# CircuitDiagram.net
KiCad netlist of a schematic drawn in EAGLE
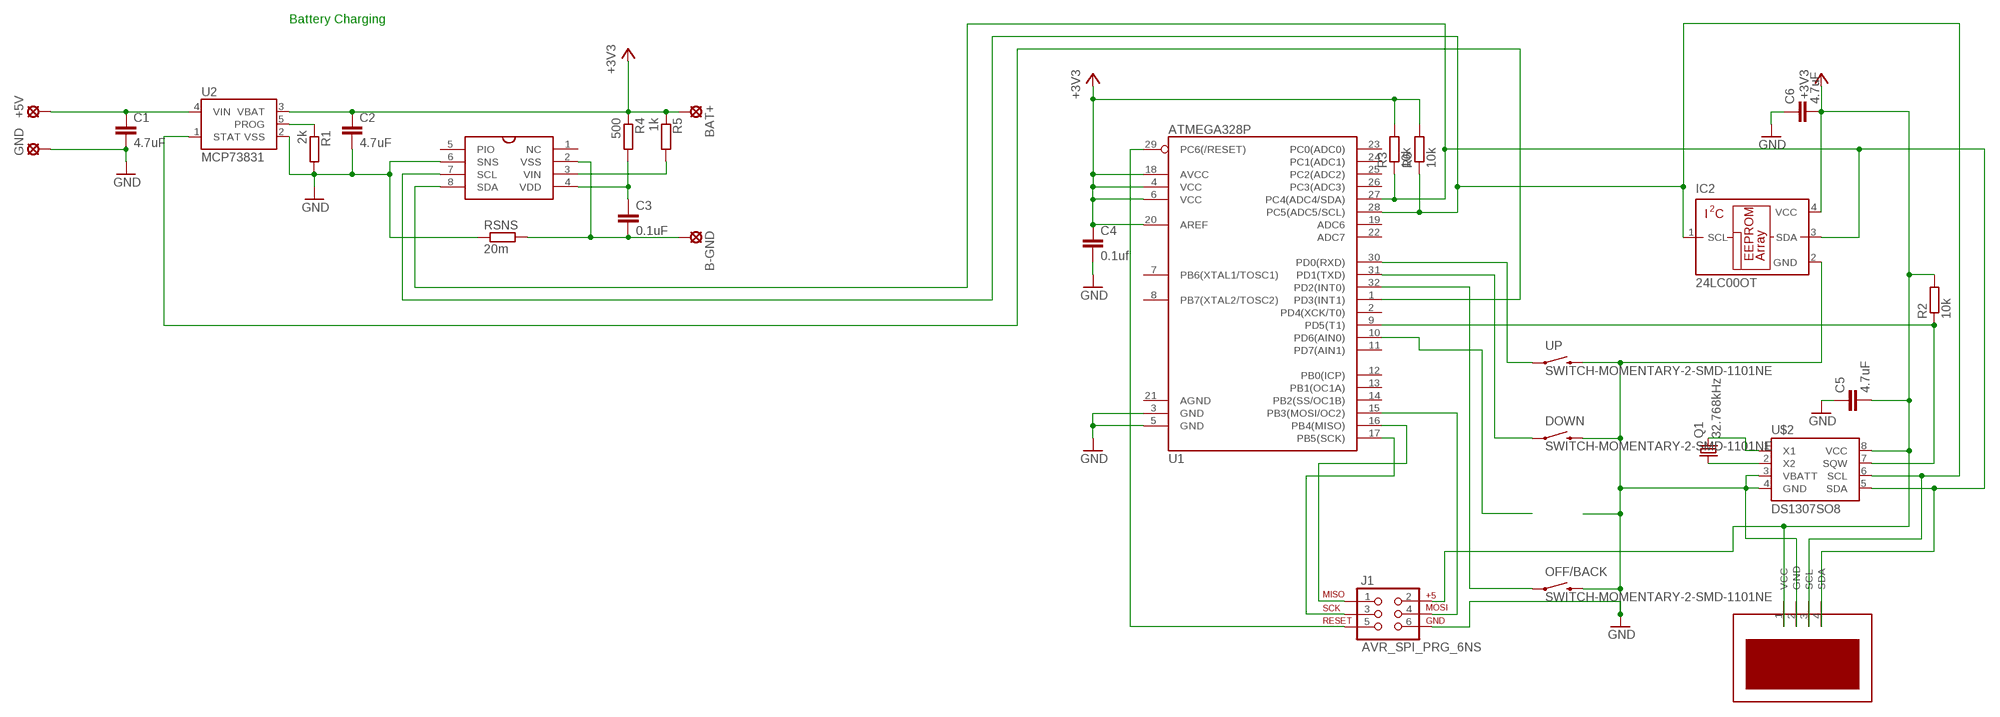
[diagram p0: schematic, sheet 1]

(export (version "E")
  (design (tool "Eeschema 10.0.6"))
  (components
    (comp (ref "+5V")
      (value "LSP10")
      (footprint "eagle-import:LSP10")
      (libsource (lib "eagle-import") (part "LSP10"))
    )
    (comp (ref "B-GND")
      (value "LSP10")
      (footprint "eagle-import:LSP10")
      (libsource (lib "eagle-import") (part "LSP10"))
    )
    (comp (ref "BAT+")
      (value "LSP10")
      (footprint "eagle-import:LSP10")
      (libsource (lib "eagle-import") (part "LSP10"))
    )
    (comp (ref "C1")
      (value "4.7uF")
      (footprint "eagle-import:C0402")
      (libsource (lib "eagle-import") (part "C-EUC0402"))
    )
    (comp (ref "C2")
      (value "4.7uF")
      (footprint "eagle-import:C0402")
      (libsource (lib "eagle-import") (part "C-EUC0402"))
    )
    (comp (ref "C3")
      (value "0.1uF")
      (footprint "eagle-import:C0402")
      (libsource (lib "eagle-import") (part "C-EUC0402"))
    )
    (comp (ref "C4")
      (value "0.1uf")
      (footprint "eagle-import:C0402")
      (libsource (lib "eagle-import") (part "C-EUC0402"))
    )
    (comp (ref "C5")
      (value "4.7uF")
      (footprint "eagle-import:C0402")
      (libsource (lib "eagle-import") (part "C-EUC0402"))
    )
    (comp (ref "C6")
      (value "4.7uF")
      (footprint "eagle-import:C1005")
      (libsource (lib "eagle-import") (part "C-EUC1005"))
    )
    (comp (ref "DOWN")
      (value "SWITCH-MOMENTARY-2-SMD-1101NE")
      (footprint "eagle-import:TACTILE-SWITCH-1101NE")
      (libsource (lib "eagle-import") (part "SWITCH-MOMENTARY-2-SMD-1101NE"))
    )
    (comp (ref "GND")
      (value "LSP10")
      (footprint "eagle-import:LSP10")
      (libsource (lib "eagle-import") (part "LSP10"))
    )
    (comp (ref "IC2")
      (value "24LC00OT")
      (footprint "eagle-import:SOT23-5L")
      (fields (field (name "MF") "MICROCHIP") (field (name "MPN") "24LC00T-I/OT"))
      (libsource (lib "eagle-import") (part "2400OTLC"))
    )
    (comp (ref "J1")
      (value "AVR_SPI_PRG_6NS")
      (footprint "eagle-import:2X3-NS")
      (libsource (lib "eagle-import") (part "AVR_SPI_PRG_6NS"))
    )
    (comp (ref "OFF/BACK")
      (value "SWITCH-MOMENTARY-2-SMD-1101NE")
      (footprint "eagle-import:TACTILE-SWITCH-1101NE")
      (libsource (lib "eagle-import") (part "SWITCH-MOMENTARY-2-SMD-1101NE"))
    )
    (comp (ref "Q1")
      (value "32.768kHz")
      (footprint "eagle-import:3.2X1.5-2-PAD")
      (libsource (lib "eagle-import") (part "CRYSTALS-NOGND-CFPX-217"))
    )
    (comp (ref "R1")
      (value "2k")
      (footprint "eagle-import:R0603")
      (libsource (lib "eagle-import") (part "R-EU_R0603"))
    )
    (comp (ref "R2")
      (value "10k")
      (footprint "eagle-import:R0603")
      (libsource (lib "eagle-import") (part "R-EU_R0603"))
    )
    (comp (ref "R3")
      (value "10k")
      (footprint "eagle-import:R0603")
      (libsource (lib "eagle-import") (part "R-EU_R0603"))
    )
    (comp (ref "R4")
      (value "500")
      (footprint "eagle-import:R0603")
      (libsource (lib "eagle-import") (part "R-EU_R0603"))
    )
    (comp (ref "R5")
      (value "1k")
      (footprint "eagle-import:R0603")
      (libsource (lib "eagle-import") (part "R-EU_R0603"))
    )
    (comp (ref "R6")
      (value "10k")
      (footprint "eagle-import:R0603")
      (libsource (lib "eagle-import") (part "R-EU_R0603"))
    )
    (comp (ref "RSNS")
      (value "20m")
      (footprint "eagle-import:R0603")
      (libsource (lib "eagle-import") (part "R-EU_R0603"))
    )
    (comp (ref "U$1")
      (value "DS2782-2")
      (footprint "eagle-import:TSSOP8")
      (libsource (lib "eagle-import") (part "DS2782-2"))
    )
    (comp (ref "U$2")
      (value "DS1307SO8")
      (footprint "eagle-import:SO08")
      (libsource (lib "eagle-import") (part "DS1307SO8"))
    )
    (comp (ref "U$3")
      (value "OLED")
      (footprint "eagle-import:OLED")
      (libsource (lib "eagle-import") (part "OLED"))
    )
    (comp (ref "U1")
      (value "ATMEGA328P")
      (footprint "eagle-import:TQFP32-08")
      (libsource (lib "eagle-import") (part "ATMEGA328_SMT"))
    )
    (comp (ref "U2")
      (value "MCP73831")
      (footprint "eagle-import:SOT23-5")
      (libsource (lib "eagle-import") (part "MCP73831"))
    )
    (comp (ref "UP")
      (value "SWITCH-MOMENTARY-2-SMD-1101NE")
      (footprint "eagle-import:TACTILE-SWITCH-1101NE")
      (libsource (lib "eagle-import") (part "SWITCH-MOMENTARY-2-SMD-1101NE"))
    )
  )
  (nets
    (net (code "1") (name "+3V3") (class "Default")
      (node (ref "BAT+") (pin "MP") (pinfunction "MP_MP") (pintype "passive"))
      (node (ref "C2") (pin "1") (pinfunction "1_1") (pintype "passive"))
      (node (ref "C4") (pin "1") (pinfunction "1_1") (pintype "passive"))
      (node (ref "C5") (pin "2") (pinfunction "2_2") (pintype "passive"))
      (node (ref "C6") (pin "2") (pinfunction "2_2") (pintype "passive"))
      (node (ref "IC2") (pin "4") (pinfunction "VCC_4") (pintype "power_in"))
      (node (ref "J1") (pin "2") (pinfunction "2_2") (pintype "passive"))
      (node (ref "R2") (pin "2") (pinfunction "2_2") (pintype "passive"))
      (node (ref "R3") (pin "2") (pinfunction "2_2") (pintype "passive"))
      (node (ref "R4") (pin "1") (pinfunction "1_1") (pintype "passive"))
      (node (ref "R5") (pin "1") (pinfunction "1_1") (pintype "passive"))
      (node (ref "R6") (pin "2") (pinfunction "2_2") (pintype "passive"))
      (node (ref "U$2") (pin "8") (pinfunction "VCC_8") (pintype "bidirectional"))
      (node (ref "U$3") (pin "1") (pinfunction "VCC_1") (pintype "bidirectional"))
      (node (ref "U1") (pin "18") (pinfunction "AVCC_18") (pintype "bidirectional"))
      (node (ref "U1") (pin "20") (pinfunction "AREF_20") (pintype "bidirectional"))
      (node (ref "U1") (pin "4") (pinfunction "VCC_4") (pintype "bidirectional"))
      (node (ref "U1") (pin "6") (pinfunction "VCC_6") (pintype "bidirectional"))
      (node (ref "U2") (pin "3") (pinfunction "VBAT_3") (pintype "power_in"))
    )
    (net (code "2") (name "GND") (class "Default")
      (node (ref "C1") (pin "2") (pinfunction "2_2") (pintype "passive"))
      (node (ref "C2") (pin "2") (pinfunction "2_2") (pintype "passive"))
      (node (ref "C4") (pin "2") (pinfunction "2_2") (pintype "passive"))
      (node (ref "C5") (pin "1") (pinfunction "1_1") (pintype "passive"))
      (node (ref "C6") (pin "1") (pinfunction "1_1") (pintype "passive"))
      (node (ref "DOWN") (pin "2") (pinfunction "2_2") (pintype "passive"))
      (node (ref "GND") (pin "MP") (pinfunction "MP_MP") (pintype "passive"))
      (node (ref "IC2") (pin "2") (pinfunction "GND_2") (pintype "power_in"))
      (node (ref "J1") (pin "6") (pinfunction "6_6") (pintype "passive"))
      (node (ref "OFF/BACK") (pin "2") (pinfunction "2_2") (pintype "passive"))
      (node (ref "R1") (pin "2") (pinfunction "2_2") (pintype "passive"))
      (node (ref "RSNS") (pin "1") (pinfunction "1_1") (pintype "passive"))
      (node (ref "U$1") (pin "6") (pinfunction "SNS_6") (pintype "bidirectional"))
      (node (ref "U$2") (pin "3") (pinfunction "VBATT_3") (pintype "bidirectional"))
      (node (ref "U$2") (pin "4") (pinfunction "GND_4") (pintype "bidirectional"))
      (node (ref "U$3") (pin "2") (pinfunction "GND_2") (pintype "bidirectional"))
      (node (ref "U1") (pin "3") (pinfunction "GND_3") (pintype "bidirectional"))
      (node (ref "U1") (pin "5") (pinfunction "GND_5") (pintype "bidirectional"))
      (node (ref "U2") (pin "2") (pinfunction "VSS_2") (pintype "power_in"))
      (node (ref "UP") (pin "2") (pinfunction "2_2") (pintype "passive"))
    )
    (net (code "3") (name "Net-(IC2-SCL)") (class "Default")
      (node (ref "IC2") (pin "1") (pinfunction "SCL_1") (pintype "input"))
      (node (ref "R6") (pin "1") (pinfunction "1_1") (pintype "passive"))
      (node (ref "U$1") (pin "7") (pinfunction "SCL_7") (pintype "bidirectional"))
      (node (ref "U$2") (pin "6") (pinfunction "SCL_6") (pintype "bidirectional"))
      (node (ref "U$3") (pin "3") (pinfunction "SCL_3") (pintype "bidirectional"))
      (node (ref "U1") (pin "28") (pinfunction "PC5(ADC5/SCL)_28") (pintype "bidirectional"))
    )
    (net (code "4") (name "Net-(IC2-SDA)") (class "Default")
      (node (ref "IC2") (pin "3") (pinfunction "SDA_3") (pintype "bidirectional"))
      (node (ref "R3") (pin "1") (pinfunction "1_1") (pintype "passive"))
      (node (ref "U$1") (pin "8") (pinfunction "SDA_8") (pintype "bidirectional"))
      (node (ref "U$2") (pin "5") (pinfunction "SDA_5") (pintype "bidirectional"))
      (node (ref "U$3") (pin "4") (pinfunction "SDA_4") (pintype "bidirectional"))
      (node (ref "U1") (pin "27") (pinfunction "PC4(ADC4/SDA)_27") (pintype "bidirectional"))
    )
    (net (code "5") (name "Net-(U$1-VDD)") (class "Default")
      (node (ref "C3") (pin "1") (pinfunction "1_1") (pintype "passive"))
      (node (ref "R4") (pin "2") (pinfunction "2_2") (pintype "passive"))
      (node (ref "U$1") (pin "4") (pinfunction "VDD_4") (pintype "bidirectional"))
    )
    (net (code "6") (name "Net-(U$1-VIN)") (class "Default")
      (node (ref "R5") (pin "2") (pinfunction "2_2") (pintype "passive"))
      (node (ref "U$1") (pin "3") (pinfunction "VIN_3") (pintype "bidirectional"))
    )
    (net (code "7") (name "Net-(U$1-VSS)") (class "Default")
      (node (ref "B-GND") (pin "MP") (pinfunction "MP_MP") (pintype "passive"))
      (node (ref "C3") (pin "2") (pinfunction "2_2") (pintype "passive"))
      (node (ref "RSNS") (pin "2") (pinfunction "2_2") (pintype "passive"))
      (node (ref "U$1") (pin "2") (pinfunction "VSS_2") (pintype "bidirectional"))
    )
    (net (code "8") (name "Net-(U$2-SQW)") (class "Default")
      (node (ref "R2") (pin "1") (pinfunction "1_1") (pintype "passive"))
      (node (ref "U$2") (pin "7") (pinfunction "SQW_7") (pintype "bidirectional"))
      (node (ref "U1") (pin "9") (pinfunction "PD5(T1)_9") (pintype "bidirectional"))
    )
    (net (code "9") (name "Net-(U$2-X1)") (class "Default")
      (node (ref "Q1") (pin "2") (pinfunction "2_2") (pintype "passive"))
      (node (ref "U$2") (pin "1") (pinfunction "X1_1") (pintype "bidirectional"))
    )
    (net (code "10") (name "Net-(U$2-X2)") (class "Default")
      (node (ref "Q1") (pin "1") (pinfunction "1_1") (pintype "passive"))
      (node (ref "U$2") (pin "2") (pinfunction "X2_2") (pintype "bidirectional"))
    )
    (net (code "11") (name "Net-(U1-PB3(MOSI{slash}OC2))") (class "Default")
      (node (ref "J1") (pin "4") (pinfunction "4_4") (pintype "passive"))
      (node (ref "U1") (pin "15") (pinfunction "PB3(MOSI/OC2)_15") (pintype "bidirectional"))
    )
    (net (code "12") (name "Net-(U1-PB4(MISO))") (class "Default")
      (node (ref "J1") (pin "1") (pinfunction "1_1") (pintype "passive"))
      (node (ref "U1") (pin "16") (pinfunction "PB4(MISO)_16") (pintype "bidirectional"))
    )
    (net (code "13") (name "Net-(U1-PB5(SCK))") (class "Default")
      (node (ref "J1") (pin "3") (pinfunction "3_3") (pintype "passive"))
      (node (ref "U1") (pin "17") (pinfunction "PB5(SCK)_17") (pintype "bidirectional"))
    )
    (net (code "14") (name "Net-(U1-PC6({slash}RESET))") (class "Default")
      (node (ref "J1") (pin "5") (pinfunction "5_5") (pintype "passive"))
      (node (ref "U1") (pin "29") (pinfunction "PC6(/RESET)_29") (pintype "bidirectional"))
    )
    (net (code "15") (name "Net-(U1-PD0(RXD))") (class "Default")
      (node (ref "U1") (pin "30") (pinfunction "PD0(RXD)_30") (pintype "bidirectional"))
      (node (ref "UP") (pin "1") (pinfunction "1_1") (pintype "passive"))
    )
    (net (code "16") (name "Net-(U1-PD1(TXD))") (class "Default")
      (node (ref "DOWN") (pin "1") (pinfunction "1_1") (pintype "passive"))
      (node (ref "U1") (pin "31") (pinfunction "PD1(TXD)_31") (pintype "bidirectional"))
    )
    (net (code "17") (name "Net-(U1-PD2(INT0))") (class "Default")
      (node (ref "OFF/BACK") (pin "1") (pinfunction "1_1") (pintype "passive"))
      (node (ref "U1") (pin "32") (pinfunction "PD2(INT0)_32") (pintype "bidirectional"))
    )
    (net (code "18") (name "Net-(U1-PD3(INT1))") (class "Default")
      (node (ref "U1") (pin "1") (pinfunction "PD3(INT1)_1") (pintype "bidirectional"))
      (node (ref "U2") (pin "1") (pinfunction "STAT_1") (pintype "output"))
    )
    (net (code "19") (name "Net-(U2-PROG)") (class "Default")
      (node (ref "R1") (pin "1") (pinfunction "1_1") (pintype "passive"))
      (node (ref "U2") (pin "5") (pinfunction "PROG_5") (pintype "input"))
    )
    (net (code "20") (name "Net-(U2-VIN)") (class "Default")
      (node (ref "+5V") (pin "MP") (pinfunction "MP_MP") (pintype "passive"))
      (node (ref "C1") (pin "1") (pinfunction "1_1") (pintype "passive"))
      (node (ref "U2") (pin "4") (pinfunction "VIN_4") (pintype "power_in"))
    )
    (net (code "21") (name "unconnected-(U$1-NC-Pad1)") (class "Default")
      (node (ref "U$1") (pin "1") (pinfunction "NC_1") (pintype "bidirectional"))
    )
    (net (code "22") (name "unconnected-(U$1-PIO-Pad5)") (class "Default")
      (node (ref "U$1") (pin "5") (pinfunction "PIO_5") (pintype "bidirectional"))
    )
    (net (code "23") (name "unconnected-(U1-ADC6-Pad19)") (class "Default")
      (node (ref "U1") (pin "19") (pinfunction "ADC6_19") (pintype "bidirectional"))
    )
    (net (code "24") (name "unconnected-(U1-ADC7-Pad22)") (class "Default")
      (node (ref "U1") (pin "22") (pinfunction "ADC7_22") (pintype "bidirectional"))
    )
    (net (code "25") (name "unconnected-(U1-AGND-Pad21)") (class "Default")
      (node (ref "U1") (pin "21") (pinfunction "AGND_21") (pintype "bidirectional"))
    )
    (net (code "26") (name "unconnected-(U1-PB0(ICP)-Pad12)") (class "Default")
      (node (ref "U1") (pin "12") (pinfunction "PB0(ICP)_12") (pintype "bidirectional"))
    )
    (net (code "27") (name "unconnected-(U1-PB1(OC1A)-Pad13)") (class "Default")
      (node (ref "U1") (pin "13") (pinfunction "PB1(OC1A)_13") (pintype "bidirectional"))
    )
    (net (code "28") (name "unconnected-(U1-PB2(SS{slash}OC1B)-Pad14)") (class "Default")
      (node (ref "U1") (pin "14") (pinfunction "PB2(SS/OC1B)_14") (pintype "bidirectional"))
    )
    (net (code "29") (name "unconnected-(U1-PB6(XTAL1{slash}TOSC1)-Pad7)") (class "Default")
      (node (ref "U1") (pin "7") (pinfunction "PB6(XTAL1/TOSC1)_7") (pintype "bidirectional"))
    )
    (net (code "30") (name "unconnected-(U1-PB7(XTAL2{slash}TOSC2)-Pad8)") (class "Default")
      (node (ref "U1") (pin "8") (pinfunction "PB7(XTAL2/TOSC2)_8") (pintype "bidirectional"))
    )
    (net (code "31") (name "unconnected-(U1-PC0(ADC0)-Pad23)") (class "Default")
      (node (ref "U1") (pin "23") (pinfunction "PC0(ADC0)_23") (pintype "bidirectional"))
    )
    (net (code "32") (name "unconnected-(U1-PC1(ADC1)-Pad24)") (class "Default")
      (node (ref "U1") (pin "24") (pinfunction "PC1(ADC1)_24") (pintype "bidirectional"))
    )
    (net (code "33") (name "unconnected-(U1-PC2(ADC2)-Pad25)") (class "Default")
      (node (ref "U1") (pin "25") (pinfunction "PC2(ADC2)_25") (pintype "bidirectional"))
    )
    (net (code "34") (name "unconnected-(U1-PC3(ADC3)-Pad26)") (class "Default")
      (node (ref "U1") (pin "26") (pinfunction "PC3(ADC3)_26") (pintype "bidirectional"))
    )
    (net (code "35") (name "unconnected-(U1-PD4(XCK{slash}T0)-Pad2)") (class "Default")
      (node (ref "U1") (pin "2") (pinfunction "PD4(XCK/T0)_2") (pintype "bidirectional"))
    )
    (net (code "36") (name "unconnected-(U1-PD6(AIN0)-Pad10)") (class "Default")
      (node (ref "U1") (pin "10") (pinfunction "PD6(AIN0)_10") (pintype "bidirectional"))
    )
    (net (code "37") (name "unconnected-(U1-PD7(AIN1)-Pad11)") (class "Default")
      (node (ref "U1") (pin "11") (pinfunction "PD7(AIN1)_11") (pintype "bidirectional"))
    )
  )
)
